# Sheet.net
KiCad netlist of a schematic drawn in Altium Designer
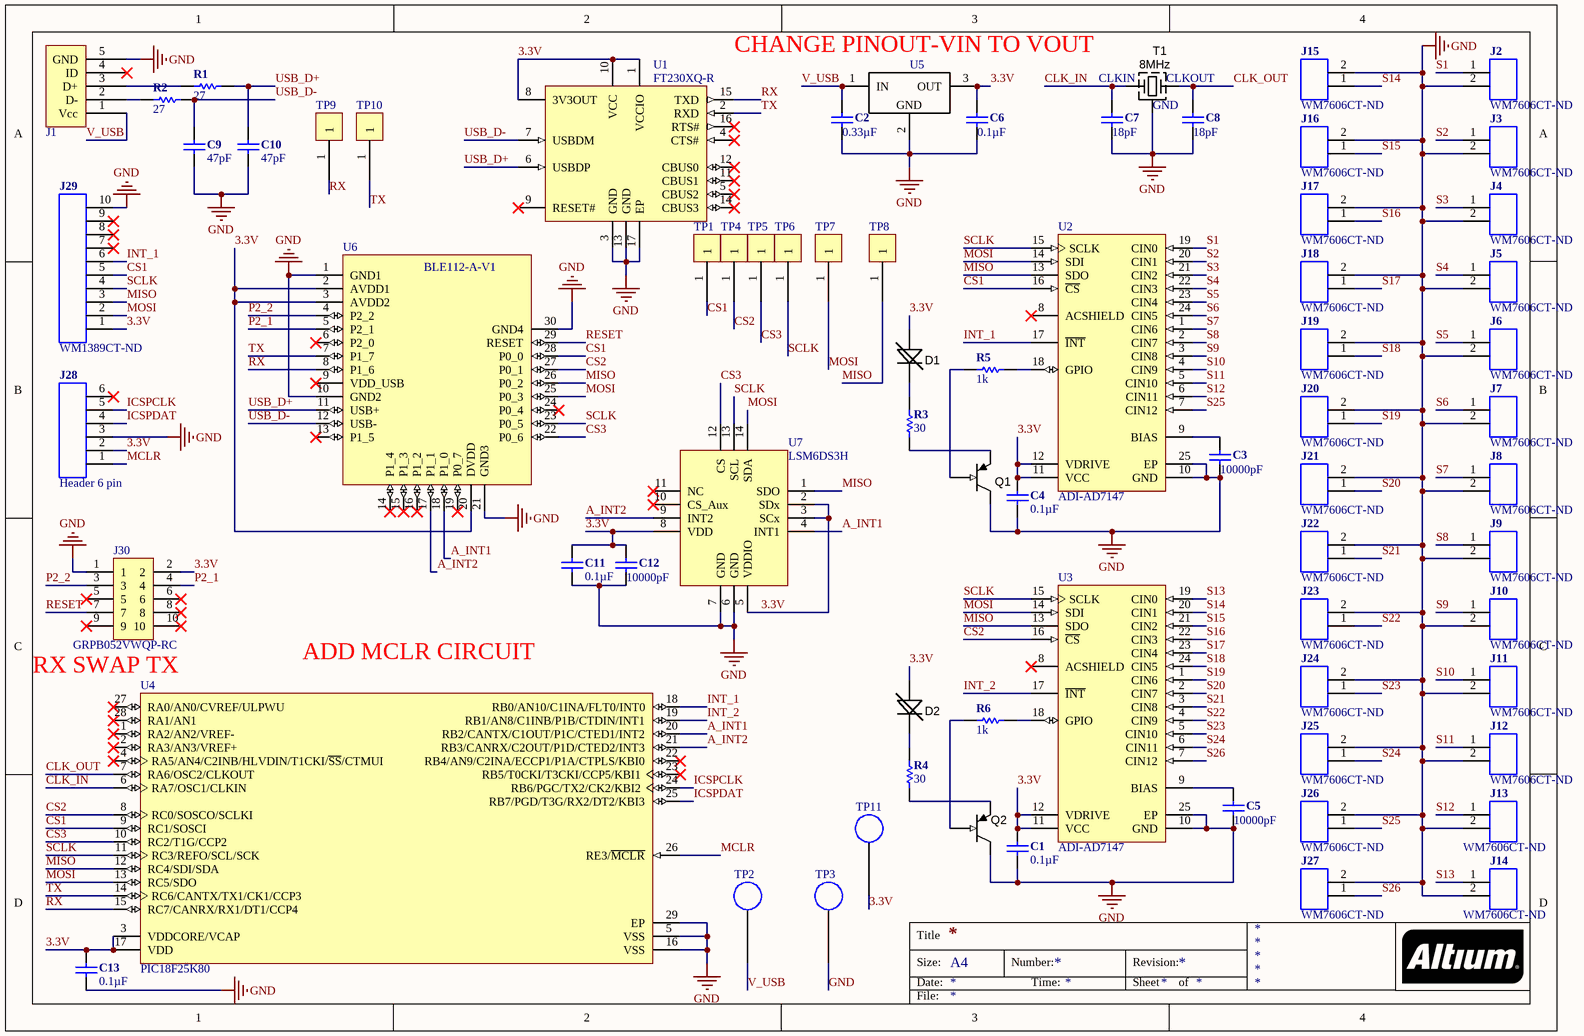
[diagram p0: Sheet.SchDoc]

(export (version "E")
  (design (tool "Eeschema 10.0.6"))
  (components
    (comp (ref "C1")
      (value "0.1µF")
      (footprint "CAP-0805(2012)-R")
      (description "___ OHM ___ mW 0805(2012) SMD")
      (fields
        (field (name "MANUFACTURER") "Yageo")
        (field (name "MANUFACTURER PART NUMBER") "CC0805KRX7R9BB104")
      )
      (libsource (lib "Glove") (part "C-0805(2012)"))
    )
    (comp (ref "C2")
      (value "0.33µF")
      (footprint "CAP-0805(2012)-R")
      (description "___ OHM ___ mW 0805(2012) SMD")
      (fields
        (field (name "MANUFACTURER") "Yageo")
        (field (name "MANUFACTURER PART NUMBER") "CC0805KKX7R7BB334")
      )
      (libsource (lib "Glove") (part "C-0805(2012)"))
    )
    (comp (ref "C3")
      (value "10000pF")
      (footprint "CAP-0805(2012)-R")
      (description "___ OHM ___ mW 0805(2012) SMD")
      (fields
        (field (name "MANUFACTURER") "Yageo")
        (field (name "MANUFACTURER PART NUMBER") "CC0805KRX7R9BB103")
      )
      (libsource (lib "Glove") (part "C-0805(2012)"))
    )
    (comp (ref "C4")
      (value "0.1µF")
      (footprint "CAP-0805(2012)-R")
      (description "___ OHM ___ mW 0805(2012) SMD")
      (fields
        (field (name "MANUFACTURER") "Yageo")
        (field (name "MANUFACTURER PART NUMBER") "CC0805KRX7R9BB104")
      )
      (libsource (lib "Glove") (part "C-0805(2012)"))
    )
    (comp (ref "C5")
      (value "10000pF")
      (footprint "CAP-0805(2012)-R")
      (description "___ OHM ___ mW 0805(2012) SMD")
      (fields
        (field (name "MANUFACTURER") "Yageo")
        (field (name "MANUFACTURER PART NUMBER") "CC0805KRX7R9BB103")
      )
      (libsource (lib "Glove") (part "C-0805(2012)"))
    )
    (comp (ref "C6")
      (value "0.1µF")
      (footprint "CAP-0805(2012)-R")
      (description "___ OHM ___ mW 0805(2012) SMD")
      (fields
        (field (name "MANUFACTURER") "Yageo")
        (field (name "MANUFACTURER PART NUMBER") "CC0805KRX7R9BB104")
      )
      (libsource (lib "Glove") (part "C-0805(2012)"))
    )
    (comp (ref "C7")
      (value "18pF")
      (footprint "CAP-0805(2012)-R")
      (description "___ OHM ___ mW 0805(2012) SMD")
      (fields
        (field (name "MANUFACTURER") "Yageo")
        (field (name "MANUFACTURER PART NUMBER") "CC0805JRNPO9BN180")
      )
      (libsource (lib "Glove") (part "C-0805(2012)"))
    )
    (comp (ref "C8")
      (value "18pF")
      (footprint "CAP-0805(2012)-R")
      (description "___ OHM ___ mW 0805(2012) SMD")
      (fields
        (field (name "MANUFACTURER") "Yageo")
        (field (name "MANUFACTURER PART NUMBER") "CC0805JRNPO9BN180")
      )
      (libsource (lib "Glove") (part "C-0805(2012)"))
    )
    (comp (ref "C9")
      (value "47pF")
      (footprint "CAP-0805(2012)-R")
      (description "___ OHM ___ mW 0805(2012) SMD")
      (fields
        (field (name "MANUFACTURER") "Yageo")
        (field (name "MANUFACTURER PART NUMBER") "CC0805JRNPO9BN470")
      )
      (libsource (lib "Glove") (part "C-0805(2012)"))
    )
    (comp (ref "C10")
      (value "47pF")
      (footprint "CAP-0805(2012)-R")
      (description "___ OHM ___ mW 0805(2012) SMD")
      (fields
        (field (name "MANUFACTURER") "Yageo")
        (field (name "MANUFACTURER PART NUMBER") "CC0805JRNPO9BN470")
      )
      (libsource (lib "Glove") (part "C-0805(2012)"))
    )
    (comp (ref "C11")
      (value "0.1µF")
      (footprint "CAP-0805(2012)-R")
      (description "___ OHM ___ mW 0805(2012) SMD")
      (fields
        (field (name "MANUFACTURER") "Yageo")
        (field (name "MANUFACTURER PART NUMBER") "CC0805KRX7R9BB104")
      )
      (libsource (lib "Glove") (part "C-0805(2012)"))
    )
    (comp (ref "C12")
      (value "10000pF")
      (footprint "CAP-0805(2012)-R")
      (description "___ OHM ___ mW 0805(2012) SMD")
      (fields
        (field (name "MANUFACTURER") "Yageo")
        (field (name "MANUFACTURER PART NUMBER") "CC0805KRX7R9BB103")
      )
      (libsource (lib "Glove") (part "C-0805(2012)"))
    )
    (comp (ref "C13")
      (value "0.1µF")
      (footprint "CAP-0805(2012)-R")
      (description "___ OHM ___ mW 0805(2012) SMD")
      (fields
        (field (name "MANUFACTURER") "Yageo")
        (field (name "MANUFACTURER PART NUMBER") "CC0805KRX7R9BB104")
      )
      (libsource (lib "Glove") (part "C-0805(2012)"))
    )
    (comp (ref "D1")
      (value "YELLOW")
      (footprint "LED-0805-A")
      (description "LED, 0805 SMD, YELLOW")
      (fields
        (field (name "MANUFACTURER") "OSRAM Opto Semiconductors Inc.")
        (field (name "MANUFACTURER PART NUMBER") "LY R976-PS-36")
      )
      (libsource (lib "Glove") (part "LED_0805_YELLOW"))
    )
    (comp (ref "D2")
      (value "YELLOW")
      (footprint "LED-0805-A")
      (description "LED, 0805 SMD, YELLOW")
      (fields
        (field (name "MANUFACTURER") "OSRAM Opto Semiconductors Inc.")
        (field (name "MANUFACTURER PART NUMBER") "LY R976-PS-36")
      )
      (libsource (lib "Glove") (part "LED_0805_YELLOW"))
    )
    (comp (ref "J1")
      (value "USB")
      (footprint "USB_Connector_5P_MICRO_USB_FCI")
      (description "USB_Connector_5P_MICRO_USB_FCI")
      (fields
        (field (name "MANUFACTURER") "Amphenol FCI")
        (field (name "MANUFACTURER PART NUMBER") "10118194-0001LF")
      )
      (libsource (lib "Glove") (part "USB"))
    )
    (comp (ref "J2")
      (value "Header 2 pin")
      (footprint "WM7606CT-ND")
      (description "Header, 2 pin, .1 pitch")
      (fields
        (field (name "MANUFACTURER") "Molex, LLC")
        (field (name "MANUFACTURER PART NUMBER") "0533980271")
        (field (name "SUPPLIER PART NUMBER 1") "WM7606CT-ND")
      )
      (libsource (lib "") (part "CON-2Pin_1"))
    )
    (comp (ref "J3")
      (value "Header 2 pin")
      (footprint "WM7606CT-ND")
      (description "Header, 2 pin, .1 pitch")
      (fields
        (field (name "MANUFACTURER") "Molex, LLC")
        (field (name "MANUFACTURER PART NUMBER") "0533980271")
        (field (name "SUPPLIER PART NUMBER 1") "WM7606CT-ND")
      )
      (libsource (lib "") (part "CON-2Pin_1"))
    )
    (comp (ref "J4")
      (value "Header 2 pin")
      (footprint "WM7606CT-ND")
      (description "Header, 2 pin, .1 pitch")
      (fields
        (field (name "MANUFACTURER") "Molex, LLC")
        (field (name "MANUFACTURER PART NUMBER") "0533980271")
        (field (name "SUPPLIER PART NUMBER 1") "WM7606CT-ND")
      )
      (libsource (lib "") (part "CON-2Pin_1"))
    )
    (comp (ref "J5")
      (value "Header 2 pin")
      (footprint "WM7606CT-ND")
      (description "Header, 2 pin, .1 pitch")
      (fields
        (field (name "MANUFACTURER") "Molex, LLC")
        (field (name "MANUFACTURER PART NUMBER") "0533980271")
        (field (name "SUPPLIER PART NUMBER 1") "WM7606CT-ND")
      )
      (libsource (lib "") (part "CON-2Pin_1"))
    )
    (comp (ref "J6")
      (value "Header 2 pin")
      (footprint "WM7606CT-ND")
      (description "Header, 2 pin, .1 pitch")
      (fields
        (field (name "MANUFACTURER") "Molex, LLC")
        (field (name "MANUFACTURER PART NUMBER") "0533980271")
        (field (name "SUPPLIER PART NUMBER 1") "WM7606CT-ND")
      )
      (libsource (lib "") (part "CON-2Pin_1"))
    )
    (comp (ref "J7")
      (value "Header 2 pin")
      (footprint "WM7606CT-ND")
      (description "Header, 2 pin, .1 pitch")
      (fields
        (field (name "MANUFACTURER") "Molex, LLC")
        (field (name "MANUFACTURER PART NUMBER") "0533980271")
        (field (name "SUPPLIER PART NUMBER 1") "WM7606CT-ND")
      )
      (libsource (lib "") (part "CON-2Pin_1"))
    )
    (comp (ref "J8")
      (value "Header 2 pin")
      (footprint "WM7606CT-ND")
      (description "Header, 2 pin, .1 pitch")
      (fields
        (field (name "MANUFACTURER") "Molex, LLC")
        (field (name "MANUFACTURER PART NUMBER") "0533980271")
        (field (name "SUPPLIER PART NUMBER 1") "WM7606CT-ND")
      )
      (libsource (lib "") (part "CON-2Pin_1"))
    )
    (comp (ref "J9")
      (value "Header 2 pin")
      (footprint "WM7606CT-ND")
      (description "Header, 2 pin, .1 pitch")
      (fields
        (field (name "MANUFACTURER") "Molex, LLC")
        (field (name "MANUFACTURER PART NUMBER") "0533980271")
        (field (name "SUPPLIER PART NUMBER 1") "WM7606CT-ND")
      )
      (libsource (lib "") (part "CON-2Pin_1"))
    )
    (comp (ref "J10")
      (value "Header 2 pin")
      (footprint "WM7606CT-ND")
      (description "Header, 2 pin, .1 pitch")
      (fields
        (field (name "MANUFACTURER") "Molex, LLC")
        (field (name "MANUFACTURER PART NUMBER") "0533980271")
        (field (name "SUPPLIER PART NUMBER 1") "WM7606CT-ND")
      )
      (libsource (lib "") (part "CON-2Pin_1"))
    )
    (comp (ref "J11")
      (value "Header 2 pin")
      (footprint "WM7606CT-ND")
      (description "Header, 2 pin, .1 pitch")
      (fields
        (field (name "MANUFACTURER") "Molex, LLC")
        (field (name "MANUFACTURER PART NUMBER") "0533980271")
        (field (name "SUPPLIER PART NUMBER 1") "WM7606CT-ND")
      )
      (libsource (lib "") (part "CON-2Pin_1"))
    )
    (comp (ref "J12")
      (value "Header 2 pin")
      (footprint "WM7606CT-ND")
      (description "Header, 2 pin, .1 pitch")
      (fields
        (field (name "MANUFACTURER") "Molex, LLC")
        (field (name "MANUFACTURER PART NUMBER") "0533980271")
        (field (name "SUPPLIER PART NUMBER 1") "WM7606CT-ND")
      )
      (libsource (lib "") (part "CON-2Pin_1"))
    )
    (comp (ref "J13")
      (value "Header 2 pin")
      (footprint "WM7606CT-ND")
      (description "Header, 2 pin, .1 pitch")
      (fields
        (field (name "MANUFACTURER") "Molex, LLC")
        (field (name "MANUFACTURER PART NUMBER") "0533980271")
        (field (name "SUPPLIER PART NUMBER 1") "WM7606CT-ND")
      )
      (libsource (lib "") (part "CON-2Pin_1"))
    )
    (comp (ref "J14")
      (value "Header 2 pin")
      (footprint "WM7606CT-ND")
      (description "Header, 2 pin, .1 pitch")
      (fields
        (field (name "MANUFACTURER") "Molex, LLC")
        (field (name "MANUFACTURER PART NUMBER") "0533980271")
        (field (name "SUPPLIER PART NUMBER 1") "WM7606CT-ND")
      )
      (libsource (lib "") (part "CON-2Pin_1"))
    )
    (comp (ref "J15")
      (value "Header 2 pin")
      (footprint "WM7606CT-ND")
      (description "Header, 2 pin, .1 pitch")
      (fields
        (field (name "MANUFACTURER") "Molex, LLC")
        (field (name "MANUFACTURER PART NUMBER") "0533980271")
        (field (name "SUPPLIER PART NUMBER 1") "WM7606CT-ND")
      )
      (libsource (lib "Glove") (part "CON-2Pin"))
    )
    (comp (ref "J16")
      (value "Header 2 pin")
      (footprint "WM7606CT-ND")
      (description "Header, 2 pin, .1 pitch")
      (fields
        (field (name "MANUFACTURER") "Molex, LLC")
        (field (name "MANUFACTURER PART NUMBER") "0533980271")
        (field (name "SUPPLIER PART NUMBER 1") "WM7606CT-ND")
      )
      (libsource (lib "Glove") (part "CON-2Pin"))
    )
    (comp (ref "J17")
      (value "Header 2 pin")
      (footprint "WM7606CT-ND")
      (description "Header, 2 pin, .1 pitch")
      (fields
        (field (name "MANUFACTURER") "Molex, LLC")
        (field (name "MANUFACTURER PART NUMBER") "0533980271")
        (field (name "SUPPLIER PART NUMBER 1") "WM7606CT-ND")
      )
      (libsource (lib "Glove") (part "CON-2Pin"))
    )
    (comp (ref "J18")
      (value "Header 2 pin")
      (footprint "WM7606CT-ND")
      (description "Header, 2 pin, .1 pitch")
      (fields
        (field (name "MANUFACTURER") "Molex, LLC")
        (field (name "MANUFACTURER PART NUMBER") "0533980271")
        (field (name "SUPPLIER PART NUMBER 1") "WM7606CT-ND")
      )
      (libsource (lib "Glove") (part "CON-2Pin"))
    )
    (comp (ref "J19")
      (value "Header 2 pin")
      (footprint "WM7606CT-ND")
      (description "Header, 2 pin, .1 pitch")
      (fields
        (field (name "MANUFACTURER") "Molex, LLC")
        (field (name "MANUFACTURER PART NUMBER") "0533980271")
        (field (name "SUPPLIER PART NUMBER 1") "WM7606CT-ND")
      )
      (libsource (lib "Glove") (part "CON-2Pin"))
    )
    (comp (ref "J20")
      (value "Header 2 pin")
      (footprint "WM7606CT-ND")
      (description "Header, 2 pin, .1 pitch")
      (fields
        (field (name "MANUFACTURER") "Molex, LLC")
        (field (name "MANUFACTURER PART NUMBER") "0533980271")
        (field (name "SUPPLIER PART NUMBER 1") "WM7606CT-ND")
      )
      (libsource (lib "Glove") (part "CON-2Pin"))
    )
    (comp (ref "J21")
      (value "Header 2 pin")
      (footprint "WM7606CT-ND")
      (description "Header, 2 pin, .1 pitch")
      (fields
        (field (name "MANUFACTURER") "Molex, LLC")
        (field (name "MANUFACTURER PART NUMBER") "0533980271")
        (field (name "SUPPLIER PART NUMBER 1") "WM7606CT-ND")
      )
      (libsource (lib "Glove") (part "CON-2Pin"))
    )
    (comp (ref "J22")
      (value "Header 2 pin")
      (footprint "WM7606CT-ND")
      (description "Header, 2 pin, .1 pitch")
      (fields
        (field (name "MANUFACTURER") "Molex, LLC")
        (field (name "MANUFACTURER PART NUMBER") "0533980271")
        (field (name "SUPPLIER PART NUMBER 1") "WM7606CT-ND")
      )
      (libsource (lib "Glove") (part "CON-2Pin"))
    )
    (comp (ref "J23")
      (value "Header 2 pin")
      (footprint "WM7606CT-ND")
      (description "Header, 2 pin, .1 pitch")
      (fields
        (field (name "MANUFACTURER") "Molex, LLC")
        (field (name "MANUFACTURER PART NUMBER") "0533980271")
        (field (name "SUPPLIER PART NUMBER 1") "WM7606CT-ND")
      )
      (libsource (lib "Glove") (part "CON-2Pin"))
    )
    (comp (ref "J24")
      (value "Header 2 pin")
      (footprint "WM7606CT-ND")
      (description "Header, 2 pin, .1 pitch")
      (fields
        (field (name "MANUFACTURER") "Molex, LLC")
        (field (name "MANUFACTURER PART NUMBER") "0533980271")
        (field (name "SUPPLIER PART NUMBER 1") "WM7606CT-ND")
      )
      (libsource (lib "Glove") (part "CON-2Pin"))
    )
    (comp (ref "J25")
      (value "Header 2 pin")
      (footprint "WM7606CT-ND")
      (description "Header, 2 pin, .1 pitch")
      (fields
        (field (name "MANUFACTURER") "Molex, LLC")
        (field (name "MANUFACTURER PART NUMBER") "0533980271")
        (field (name "SUPPLIER PART NUMBER 1") "WM7606CT-ND")
      )
      (libsource (lib "Glove") (part "CON-2Pin"))
    )
    (comp (ref "J26")
      (value "Header 2 pin")
      (footprint "WM7606CT-ND")
      (description "Header, 2 pin, .1 pitch")
      (fields
        (field (name "MANUFACTURER") "Molex, LLC")
        (field (name "MANUFACTURER PART NUMBER") "0533980271")
        (field (name "SUPPLIER PART NUMBER 1") "WM7606CT-ND")
      )
      (libsource (lib "Glove") (part "CON-2Pin"))
    )
    (comp (ref "J27")
      (value "Header 2 pin")
      (footprint "WM7606CT-ND")
      (description "Header, 2 pin, .1 pitch")
      (fields
        (field (name "MANUFACTURER") "Molex, LLC")
        (field (name "MANUFACTURER PART NUMBER") "0533980271")
        (field (name "SUPPLIER PART NUMBER 1") "WM7606CT-ND")
      )
      (libsource (lib "Glove") (part "CON-2Pin"))
    )
    (comp (ref "J28")
      (value "Header 6 pin")
      (footprint "HEADER-6-100mil")
      (description "Header, 6 pin, .1 pitch")
      (fields
        (field (name "MANUFACTURER") "Amphenol FCI")
        (field (name "MANUFACTURER PART NUMBER") "68000-406HLF")
      )
      (libsource (lib "Glove") (part "CON-6Pin-100Mil"))
    )
    (comp (ref "J29")
      (value "Header 10 pin")
      (footprint "MOLEX-503480-1000")
      (description "Header, 10 pin, .50mm pitch")
      (fields
        (field (name "MANUFACTURER") "Molex, LLC")
        (field (name "MANUFACTURER PART NUMBER") "5034801000")
        (field (name "SUPPLIER PART NUMBER 1") "WM1389CT-ND")
      )
      (libsource (lib "Glove") (part "WM1389CT-ND"))
    )
    (comp (ref "J30")
      (value "GRPB052VWQP-RC")
      (footprint "GRPB052VWQP-RC")
      (description "CONN HEADER .050\" 10PS DL SMD AU")
      (fields (field (name "MANUFACTURER") "Sullins Connector Solutions"))
      (libsource (lib "UCSD Protolab") (part "GRPB052VWQP-RC"))
    )
    (comp (ref "Q1")
      (value "~")
      (footprint "SOT23-3")
      (description "Transistor PNP")
      (fields
        (field (name "MANUFACTURER") "Diodes Incorporated")
        (field (name "MANUFACTURER PART NUMBER") "FMMT591TA")
      )
      (libsource (lib "Glove") (part "FMMT591CT-ND"))
    )
    (comp (ref "Q2")
      (value "~")
      (footprint "SOT23-3")
      (description "Transistor PNP")
      (fields
        (field (name "MANUFACTURER") "Diodes Incorporated")
        (field (name "MANUFACTURER PART NUMBER") "FMMT591TA")
      )
      (libsource (lib "Glove") (part "FMMT591CT-ND"))
    )
    (comp (ref "R1")
      (value "27")
      (footprint "R-0805(2012)-R")
      (description "___ OHM ___ mW 0805(2012) SMD")
      (fields
        (field (name "MANUFACTURER") "Yageo")
        (field (name "MANUFACTURER PART NUMBER") "RC0805JR-0727RL")
      )
      (libsource (lib "Glove") (part "R-0805(2012)"))
    )
    (comp (ref "R2")
      (value "27")
      (footprint "R-0805(2012)-R")
      (description "___ OHM ___ mW 0805(2012) SMD")
      (fields
        (field (name "MANUFACTURER") "Yageo")
        (field (name "MANUFACTURER PART NUMBER") "RC0805JR-0727RL")
      )
      (libsource (lib "Glove") (part "R-0805(2012)"))
    )
    (comp (ref "R3")
      (value "30")
      (footprint "R-0805(2012)-R")
      (description "___ OHM ___ mW 0805(2012) SMD")
      (fields
        (field (name "MANUFACTURER") "Yageo")
        (field (name "MANUFACTURER PART NUMBER") "RC0805JR-0730RL")
      )
      (libsource (lib "Glove") (part "R-0805(2012)"))
    )
    (comp (ref "R4")
      (value "30")
      (footprint "R-0805(2012)-R")
      (description "___ OHM ___ mW 0805(2012) SMD")
      (fields
        (field (name "MANUFACTURER") "Yageo")
        (field (name "MANUFACTURER PART NUMBER") "RC0805JR-0730RL")
      )
      (libsource (lib "Glove") (part "R-0805(2012)"))
    )
    (comp (ref "R5")
      (value "1k")
      (footprint "R-0805(2012)-R")
      (description "___ OHM ___ mW 0805(2012) SMD")
      (fields
        (field (name "MANUFACTURER") "Yageo")
        (field (name "MANUFACTURER PART NUMBER") "RC0805JR-071KL")
      )
      (libsource (lib "Glove") (part "R-0805(2012)"))
    )
    (comp (ref "R6")
      (value "1k")
      (footprint "R-0805(2012)-R")
      (description "___ OHM ___ mW 0805(2012) SMD")
      (fields
        (field (name "MANUFACTURER") "Yageo")
        (field (name "MANUFACTURER PART NUMBER") "RC0805JR-071KL")
      )
      (libsource (lib "Glove") (part "R-0805(2012)"))
    )
    (comp (ref "T1")
      (value "8MHz")
      (footprint "CRYSTAL-8MHZ")
      (description "Oscillator Crystal 8MHz 10ppm")
      (fields
        (field (name "MANUFACTURER") "Abracon LLC")
        (field (name "MANUFACTURER PART NUMBER") "ABMM2-8.000MHZ-E2-T")
      )
      (libsource (lib "Glove") (part "CRYSTAL_8MHz"))
    )
    (comp (ref "TP1")
      (value "Test Point")
      (footprint "Test Point")
      (description "Test Point Hole")
      (fields
        (field (name "MANUFACTURER") "Keystone Electronics")
        (field (name "MANUFACTURER PART NUMBER") "5000")
      )
      (libsource (lib "Glove") (part "Test Point"))
    )
    (comp (ref "TP2")
      (value "S1751-46R")
      (footprint "S1751-46R")
      (description "PC TEST POINT TIN SMD")
      (fields (field (name "MANUFACTURER") "Harwin Inc."))
      (libsource (lib "Glove") (part "S1751-46R"))
    )
    (comp (ref "TP3")
      (value "S1751-46R")
      (footprint "S1751-46R")
      (description "PC TEST POINT TIN SMD")
      (fields (field (name "MANUFACTURER") "Harwin Inc."))
      (libsource (lib "Glove") (part "S1751-46R"))
    )
    (comp (ref "TP4")
      (value "Test Point")
      (footprint "Test Point")
      (description "Test Point Hole")
      (fields
        (field (name "MANUFACTURER") "Keystone Electronics")
        (field (name "MANUFACTURER PART NUMBER") "5000")
      )
      (libsource (lib "Glove") (part "Test Point"))
    )
    (comp (ref "TP5")
      (value "Test Point")
      (footprint "Test Point")
      (description "Test Point Hole")
      (fields
        (field (name "MANUFACTURER") "Keystone Electronics")
        (field (name "MANUFACTURER PART NUMBER") "5000")
      )
      (libsource (lib "Glove") (part "Test Point"))
    )
    (comp (ref "TP6")
      (value "Test Point")
      (footprint "Test Point")
      (description "Test Point Hole")
      (fields
        (field (name "MANUFACTURER") "Keystone Electronics")
        (field (name "MANUFACTURER PART NUMBER") "5000")
      )
      (libsource (lib "Glove") (part "Test Point"))
    )
    (comp (ref "TP7")
      (value "Test Point")
      (footprint "Test Point")
      (description "Test Point Hole")
      (fields
        (field (name "MANUFACTURER") "Keystone Electronics")
        (field (name "MANUFACTURER PART NUMBER") "5000")
      )
      (libsource (lib "Glove") (part "Test Point"))
    )
    (comp (ref "TP8")
      (value "Test Point")
      (footprint "Test Point")
      (description "Test Point Hole")
      (fields
        (field (name "MANUFACTURER") "Keystone Electronics")
        (field (name "MANUFACTURER PART NUMBER") "5000")
      )
      (libsource (lib "Glove") (part "Test Point"))
    )
    (comp (ref "TP9")
      (value "Test Point")
      (footprint "Test Point")
      (description "Test Point Hole")
      (fields
        (field (name "MANUFACTURER") "Keystone Electronics")
        (field (name "MANUFACTURER PART NUMBER") "5000")
      )
      (libsource (lib "Glove") (part "Test Point"))
    )
    (comp (ref "TP10")
      (value "Test Point")
      (footprint "Test Point")
      (description "Test Point Hole")
      (fields
        (field (name "MANUFACTURER") "Keystone Electronics")
        (field (name "MANUFACTURER PART NUMBER") "5000")
      )
      (libsource (lib "Glove") (part "Test Point"))
    )
    (comp (ref "TP11")
      (value "S1751-46R")
      (footprint "S1751-46R")
      (description "PC TEST POINT TIN SMD")
      (fields (field (name "MANUFACTURER") "Harwin Inc."))
      (libsource (lib "Glove") (part "S1751-46R"))
    )
    (comp (ref "U1")
      (value "FT230XQ-R")
      (footprint "QFN-16")
      (fields (field (name "MANUFACTURER") "FTDI, Future Technology Devices International Ltd"))
      (libsource (lib "Glove") (part "FT230XQ-R"))
    )
    (comp (ref "U2")
      (value "ADI-AD7147")
      (footprint "LFCSP_WQ")
      (fields
        (field (name "MANUFACTURER") "Analog Devices Inc.")
        (field (name "MANUFACTURER PART NUMBER") "AD7147PACPZ-500R7")
      )
      (libsource (lib "Glove") (part "ADI-AD7147"))
    )
    (comp (ref "U3")
      (value "ADI-AD7147")
      (footprint "LFCSP_WQ")
      (fields
        (field (name "MANUFACTURER") "Analog Devices Inc.")
        (field (name "MANUFACTURER PART NUMBER") "AD7147PACPZ-500R7")
      )
      (libsource (lib "Glove") (part "ADI-AD7147"))
    )
    (comp (ref "U4")
      (value "PIC18F25K80")
      (footprint "MCHP-QFN-S-MM28_N")
      (fields
        (field (name "MANUFACTURER") "Microchip Technology")
        (field (name "MANUFACTURER PART NUMBER") "PIC18F25K80T-I/MM")
      )
      (libsource (lib "Glove") (part "PIC18F25K80"))
    )
    (comp (ref "U5")
      (value "L78L33ACUTR")
      (footprint "SOT89-3")
      (fields (field (name "MANUFACTURER") "STMicroelectronics"))
      (libsource (lib "Glove") (part "L78L33ACUTR"))
    )
    (comp (ref "U6")
      (value "BLE112-A-V1")
      (footprint "BLE112-A-V1")
      (description "CLASS 2 BLTOOTH 4.0 MODULE")
      (fields (field (name "MANUFACTURER") "Silicon Labs"))
      (libsource (lib "UCSD Protolab") (part "BLE112-A-V1"))
    )
    (comp (ref "U7")
      (value "LSM6DS3H")
      (footprint "LGA-14")
      (description "3D accelerometer and 3D gyroscope")
      (fields
        (field (name "MANUFACTURER") "STMicroelectronics")
        (field (name "MANUFACTURER PART NUMBER") "LSM6DS3HTR")
      )
      (libsource (lib "Glove") (part "LSM6DS3H"))
    )
  )
  (nets
    (net (code "1") (name "/3.3V") (class "Default")
      (node (ref "C1") (pin "1") (pinfunction "1_1") (pintype "passive"))
      (node (ref "C11") (pin "2") (pinfunction "2_2") (pintype "passive"))
      (node (ref "C12") (pin "2") (pinfunction "2_2") (pintype "passive"))
      (node (ref "C13") (pin "1") (pinfunction "1_1") (pintype "passive"))
      (node (ref "C4") (pin "1") (pinfunction "1_1") (pintype "passive"))
      (node (ref "C6") (pin "1") (pinfunction "1_1") (pintype "passive"))
      (node (ref "D1") (pin "A") (pinfunction "A_A") (pintype "passive"))
      (node (ref "D2") (pin "A") (pinfunction "A_A") (pintype "passive"))
      (node (ref "J28") (pin "2") (pinfunction "2_2") (pintype "passive"))
      (node (ref "J29") (pin "1") (pinfunction "1_1") (pintype "passive"))
      (node (ref "J30") (pin "2") (pinfunction "2_2") (pintype "passive"))
      (node (ref "TP11") (pin "1") (pinfunction "1_1") (pintype "passive"))
      (node (ref "U1") (pin "1") (pinfunction "VCCIO_1") (pintype "power_in"))
      (node (ref "U1") (pin "10") (pinfunction "VCC_10") (pintype "power_in"))
      (node (ref "U1") (pin "8") (pinfunction "3V3OUT_8") (pintype "power_in"))
      (node (ref "U2") (pin "11") (pinfunction "VCC_11") (pintype "power_in"))
      (node (ref "U2") (pin "12") (pinfunction "VDRIVE_12") (pintype "power_in"))
      (node (ref "U3") (pin "11") (pinfunction "VCC_11") (pintype "power_in"))
      (node (ref "U3") (pin "12") (pinfunction "VDRIVE_12") (pintype "power_in"))
      (node (ref "U4") (pin "17") (pinfunction "VDD_17") (pintype "power_in"))
      (node (ref "U4") (pin "3") (pinfunction "VDDCORE/VCAP_3") (pintype "power_in"))
      (node (ref "U5") (pin "3") (pinfunction "OUT_3") (pintype "power_in"))
      (node (ref "U6") (pin "2") (pinfunction "AVDD1_2") (pintype "power_in"))
      (node (ref "U6") (pin "20") (pinfunction "DVDD_20") (pintype "power_in"))
      (node (ref "U6") (pin "3") (pinfunction "AVDD2_3") (pintype "power_in"))
      (node (ref "U7") (pin "2") (pinfunction "SDx_2") (pintype "passive"))
      (node (ref "U7") (pin "3") (pinfunction "SCx_3") (pintype "passive"))
      (node (ref "U7") (pin "5") (pinfunction "VDDIO_5") (pintype "passive"))
      (node (ref "U7") (pin "8") (pinfunction "VDD_8") (pintype "passive"))
    )
    (net (code "2") (name "/A_INT1") (class "Default")
      (node (ref "U4") (pin "20") (pinfunction "RB2/CANTX/C1OUT/P1C/CTED1/INT2_20") (pintype "bidirectional"))
      (node (ref "U6") (pin "18") (pinfunction "P1_0_18") (pintype "bidirectional"))
      (node (ref "U7") (pin "4") (pinfunction "INT1_4") (pintype "passive"))
    )
    (net (code "3") (name "/A_INT2") (class "Default")
      (node (ref "U4") (pin "21") (pinfunction "RB3/CANRX/C2OUT/P1D/CTED2/INT3_21") (pintype "bidirectional"))
      (node (ref "U6") (pin "17") (pinfunction "P1_1_17") (pintype "bidirectional"))
      (node (ref "U7") (pin "9") (pinfunction "INT2_9") (pintype "passive"))
    )
    (net (code "4") (name "/CLK_IN") (class "Default")
      (node (ref "C7") (pin "1") (pinfunction "1_1") (pintype "passive"))
      (node (ref "T1") (pin "1") (pinfunction "CLKIN_1") (pintype "passive"))
      (node (ref "U4") (pin "6") (pinfunction "RA7/OSC1/CLKIN_6") (pintype "bidirectional"))
    )
    (net (code "5") (name "/CLK_OUT") (class "Default")
      (node (ref "C8") (pin "1") (pinfunction "1_1") (pintype "passive"))
      (node (ref "T1") (pin "3") (pinfunction "X_3") (pintype "passive"))
      (node (ref "U4") (pin "7") (pinfunction "RA6/OSC2/CLKOUT_7") (pintype "bidirectional"))
    )
    (net (code "6") (name "/CS1") (class "Default")
      (node (ref "J29") (pin "5") (pinfunction "5_5") (pintype "passive"))
      (node (ref "TP1") (pin "1") (pinfunction "1_1") (pintype "passive"))
      (node (ref "U2") (pin "16") (pinfunction "~{CS}_16") (pintype "input"))
      (node (ref "U4") (pin "9") (pinfunction "RC1/SOSCI_9") (pintype "bidirectional"))
      (node (ref "U6") (pin "28") (pinfunction "P0_0_28") (pintype "bidirectional"))
    )
    (net (code "7") (name "/CS2") (class "Default")
      (node (ref "TP4") (pin "1") (pinfunction "1_1") (pintype "passive"))
      (node (ref "U3") (pin "16") (pinfunction "~{CS}_16") (pintype "input"))
      (node (ref "U4") (pin "8") (pinfunction "RC0/SOSCO/SCLKI_8") (pintype "bidirectional"))
      (node (ref "U6") (pin "27") (pinfunction "P0_1_27") (pintype "bidirectional"))
    )
    (net (code "8") (name "/CS3") (class "Default")
      (node (ref "TP5") (pin "1") (pinfunction "1_1") (pintype "passive"))
      (node (ref "U4") (pin "10") (pinfunction "RC2/T1G/CCP2_10") (pintype "bidirectional"))
      (node (ref "U6") (pin "22") (pinfunction "P0_6_22") (pintype "bidirectional"))
      (node (ref "U7") (pin "12") (pinfunction "CS_12") (pintype "passive"))
    )
    (net (code "9") (name "/ICSPCLK") (class "Default")
      (node (ref "J28") (pin "5") (pinfunction "5_5") (pintype "passive"))
      (node (ref "U4") (pin "24") (pinfunction "RB6/PGC/TX2/CK2/KBI2_24") (pintype "bidirectional"))
    )
    (net (code "10") (name "/ICSPDAT") (class "Default")
      (node (ref "J28") (pin "4") (pinfunction "4_4") (pintype "passive"))
      (node (ref "U4") (pin "25") (pinfunction "RB7/PGD/T3G/RX2/DT2/KBI3_25") (pintype "bidirectional"))
    )
    (net (code "11") (name "/INT_1") (class "Default")
      (node (ref "J29") (pin "6") (pinfunction "6_6") (pintype "passive"))
      (node (ref "U2") (pin "17") (pinfunction "~{INT}_17") (pintype "open_collector"))
      (node (ref "U4") (pin "18") (pinfunction "RB0/AN10/C1INA/FLT0/INT0_18") (pintype "bidirectional"))
    )
    (net (code "12") (name "/INT_2") (class "Default")
      (node (ref "U3") (pin "17") (pinfunction "~{INT}_17") (pintype "open_collector"))
      (node (ref "U4") (pin "19") (pinfunction "RB1/AN8/C1INB/P1B/CTDIN/INT1_19") (pintype "bidirectional"))
    )
    (net (code "13") (name "/MCLR") (class "Default")
      (node (ref "J28") (pin "1") (pinfunction "1_1") (pintype "passive"))
      (node (ref "U4") (pin "26") (pinfunction "RE3/~{MCLR}_26") (pintype "input"))
    )
    (net (code "14") (name "/MISO") (class "Default")
      (node (ref "J29") (pin "3") (pinfunction "3_3") (pintype "passive"))
      (node (ref "TP8") (pin "1") (pinfunction "1_1") (pintype "passive"))
      (node (ref "U2") (pin "13") (pinfunction "SDO_13") (pintype "tri_state"))
      (node (ref "U3") (pin "13") (pinfunction "SDO_13") (pintype "tri_state"))
      (node (ref "U4") (pin "12") (pinfunction "RC4/SDI/SDA_12") (pintype "bidirectional"))
      (node (ref "U6") (pin "26") (pinfunction "P0_2_26") (pintype "bidirectional"))
      (node (ref "U7") (pin "1") (pinfunction "SDO_1") (pintype "passive"))
    )
    (net (code "15") (name "/MOSI") (class "Default")
      (node (ref "J29") (pin "2") (pinfunction "2_2") (pintype "passive"))
      (node (ref "TP7") (pin "1") (pinfunction "1_1") (pintype "passive"))
      (node (ref "U2") (pin "14") (pinfunction "SDI_14") (pintype "input"))
      (node (ref "U3") (pin "14") (pinfunction "SDI_14") (pintype "input"))
      (node (ref "U4") (pin "13") (pinfunction "RC5/SDO_13") (pintype "bidirectional"))
      (node (ref "U6") (pin "25") (pinfunction "P0_3_25") (pintype "bidirectional"))
      (node (ref "U7") (pin "14") (pinfunction "SDA_14") (pintype "passive"))
    )
    (net (code "16") (name "/P2_1") (class "Default")
      (node (ref "J30") (pin "4") (pinfunction "4_4") (pintype "passive"))
      (node (ref "U6") (pin "5") (pinfunction "P2_1_5") (pintype "bidirectional"))
    )
    (net (code "17") (name "/P2_2") (class "Default")
      (node (ref "J30") (pin "3") (pinfunction "3_3") (pintype "passive"))
      (node (ref "U6") (pin "4") (pinfunction "P2_2_4") (pintype "bidirectional"))
    )
    (net (code "18") (name "/RESET") (class "Default")
      (node (ref "J30") (pin "7") (pinfunction "7_7") (pintype "passive"))
      (node (ref "U6") (pin "29") (pinfunction "RESET_29") (pintype "bidirectional"))
    )
    (net (code "19") (name "/RX") (class "Default")
      (node (ref "TP9") (pin "1") (pinfunction "1_1") (pintype "passive"))
      (node (ref "U1") (pin "15") (pinfunction "TXD_15") (pintype "output"))
      (node (ref "U4") (pin "15") (pinfunction "RC7/CANRX/RX1/DT1/CCP4_15") (pintype "bidirectional"))
      (node (ref "U6") (pin "8") (pinfunction "P1_6_8") (pintype "bidirectional"))
    )
    (net (code "20") (name "/S1") (class "Default")
      (node (ref "J2") (pin "1") (pinfunction "1_1") (pintype "passive"))
      (node (ref "U2") (pin "19") (pinfunction "CIN0_19") (pintype "input"))
    )
    (net (code "21") (name "/S2") (class "Default")
      (node (ref "J3") (pin "1") (pinfunction "1_1") (pintype "passive"))
      (node (ref "U2") (pin "20") (pinfunction "CIN1_20") (pintype "input"))
    )
    (net (code "22") (name "/S3") (class "Default")
      (node (ref "J4") (pin "1") (pinfunction "1_1") (pintype "passive"))
      (node (ref "U2") (pin "21") (pinfunction "CIN2_21") (pintype "input"))
    )
    (net (code "23") (name "/S4") (class "Default")
      (node (ref "J5") (pin "1") (pinfunction "1_1") (pintype "passive"))
      (node (ref "U2") (pin "22") (pinfunction "CIN3_22") (pintype "input"))
    )
    (net (code "24") (name "/S5") (class "Default")
      (node (ref "J6") (pin "1") (pinfunction "1_1") (pintype "passive"))
      (node (ref "U2") (pin "23") (pinfunction "CIN4_23") (pintype "input"))
    )
    (net (code "25") (name "/S6") (class "Default")
      (node (ref "J7") (pin "1") (pinfunction "1_1") (pintype "passive"))
      (node (ref "U2") (pin "24") (pinfunction "CIN5_24") (pintype "input"))
    )
    (net (code "26") (name "/S7") (class "Default")
      (node (ref "J8") (pin "1") (pinfunction "1_1") (pintype "passive"))
      (node (ref "U2") (pin "1") (pinfunction "CIN6_1") (pintype "input"))
    )
    (net (code "27") (name "/S8") (class "Default")
      (node (ref "J9") (pin "1") (pinfunction "1_1") (pintype "passive"))
      (node (ref "U2") (pin "2") (pinfunction "CIN7_2") (pintype "input"))
    )
    (net (code "28") (name "/S9") (class "Default")
      (node (ref "J10") (pin "1") (pinfunction "1_1") (pintype "passive"))
      (node (ref "U2") (pin "3") (pinfunction "CIN8_3") (pintype "input"))
    )
    (net (code "29") (name "/S10") (class "Default")
      (node (ref "J11") (pin "1") (pinfunction "1_1") (pintype "passive"))
      (node (ref "U2") (pin "4") (pinfunction "CIN9_4") (pintype "input"))
    )
    (net (code "30") (name "/S11") (class "Default")
      (node (ref "J12") (pin "1") (pinfunction "1_1") (pintype "passive"))
      (node (ref "U2") (pin "5") (pinfunction "CIN10_5") (pintype "input"))
    )
    (net (code "31") (name "/S12") (class "Default")
      (node (ref "J13") (pin "1") (pinfunction "1_1") (pintype "passive"))
      (node (ref "U2") (pin "6") (pinfunction "CIN11_6") (pintype "input"))
    )
    (net (code "32") (name "/S13") (class "Default")
      (node (ref "J14") (pin "1") (pinfunction "1_1") (pintype "passive"))
      (node (ref "U3") (pin "19") (pinfunction "CIN0_19") (pintype "input"))
    )
    (net (code "33") (name "/S14") (class "Default")
      (node (ref "J15") (pin "1") (pinfunction "1_1") (pintype "passive"))
      (node (ref "U3") (pin "20") (pinfunction "CIN1_20") (pintype "input"))
    )
    (net (code "34") (name "/S15") (class "Default")
      (node (ref "J16") (pin "1") (pinfunction "1_1") (pintype "passive"))
      (node (ref "U3") (pin "21") (pinfunction "CIN2_21") (pintype "input"))
    )
    (net (code "35") (name "/S16") (class "Default")
      (node (ref "J17") (pin "1") (pinfunction "1_1") (pintype "passive"))
      (node (ref "U3") (pin "22") (pinfunction "CIN3_22") (pintype "input"))
    )
    (net (code "36") (name "/S17") (class "Default")
      (node (ref "J18") (pin "1") (pinfunction "1_1") (pintype "passive"))
      (node (ref "U3") (pin "23") (pinfunction "CIN4_23") (pintype "input"))
    )
    (net (code "37") (name "/S18") (class "Default")
      (node (ref "J19") (pin "1") (pinfunction "1_1") (pintype "passive"))
      (node (ref "U3") (pin "24") (pinfunction "CIN5_24") (pintype "input"))
    )
    (net (code "38") (name "/S19") (class "Default")
      (node (ref "J20") (pin "1") (pinfunction "1_1") (pintype "passive"))
      (node (ref "U3") (pin "1") (pinfunction "CIN6_1") (pintype "input"))
    )
    (net (code "39") (name "/S20") (class "Default")
      (node (ref "J21") (pin "1") (pinfunction "1_1") (pintype "passive"))
      (node (ref "U3") (pin "2") (pinfunction "CIN7_2") (pintype "input"))
    )
    (net (code "40") (name "/S21") (class "Default")
      (node (ref "J22") (pin "1") (pinfunction "1_1") (pintype "passive"))
      (node (ref "U3") (pin "3") (pinfunction "CIN8_3") (pintype "input"))
    )
    (net (code "41") (name "/S22") (class "Default")
      (node (ref "J23") (pin "1") (pinfunction "1_1") (pintype "passive"))
      (node (ref "U3") (pin "4") (pinfunction "CIN9_4") (pintype "input"))
    )
    (net (code "42") (name "/S23") (class "Default")
      (node (ref "J24") (pin "1") (pinfunction "1_1") (pintype "passive"))
      (node (ref "U3") (pin "5") (pinfunction "CIN10_5") (pintype "input"))
    )
    (net (code "43") (name "/S24") (class "Default")
      (node (ref "J25") (pin "1") (pinfunction "1_1") (pintype "passive"))
      (node (ref "U3") (pin "6") (pinfunction "CIN11_6") (pintype "input"))
    )
    (net (code "44") (name "/S25") (class "Default")
      (node (ref "J26") (pin "1") (pinfunction "1_1") (pintype "passive"))
      (node (ref "U2") (pin "7") (pinfunction "CIN12_7") (pintype "input"))
    )
    (net (code "45") (name "/S26") (class "Default")
      (node (ref "J27") (pin "1") (pinfunction "1_1") (pintype "passive"))
      (node (ref "U3") (pin "7") (pinfunction "CIN12_7") (pintype "input"))
    )
    (net (code "46") (name "/SCLK") (class "Default")
      (node (ref "J29") (pin "4") (pinfunction "4_4") (pintype "passive"))
      (node (ref "TP6") (pin "1") (pinfunction "1_1") (pintype "passive"))
      (node (ref "U2") (pin "15") (pinfunction "SCLK_15") (pintype "input"))
      (node (ref "U3") (pin "15") (pinfunction "SCLK_15") (pintype "input"))
      (node (ref "U4") (pin "11") (pinfunction "RC3/REFO/SCL/SCK_11") (pintype "bidirectional"))
      (node (ref "U6") (pin "23") (pinfunction "P0_5_23") (pintype "bidirectional"))
      (node (ref "U7") (pin "13") (pinfunction "SCL_13") (pintype "passive"))
    )
    (net (code "47") (name "/TX") (class "Default")
      (node (ref "TP10") (pin "1") (pinfunction "1_1") (pintype "passive"))
      (node (ref "U1") (pin "2") (pinfunction "RXD_2") (pintype "input"))
      (node (ref "U4") (pin "14") (pinfunction "RC6/CANTX/TX1/CK1/CCP3_14") (pintype "bidirectional"))
      (node (ref "U6") (pin "7") (pinfunction "P1_7_7") (pintype "bidirectional"))
    )
    (net (code "48") (name "/USB_D+") (class "Default")
      (node (ref "C10") (pin "2") (pinfunction "2_2") (pintype "passive"))
      (node (ref "R1") (pin "2") (pinfunction "2_2") (pintype "passive"))
      (node (ref "U1") (pin "6") (pinfunction "USBDP_6") (pintype "input"))
      (node (ref "U6") (pin "11") (pinfunction "USB+_11") (pintype "bidirectional"))
    )
    (net (code "49") (name "/USB_D-") (class "Default")
      (node (ref "C9") (pin "2") (pinfunction "2_2") (pintype "passive"))
      (node (ref "R2") (pin "2") (pinfunction "2_2") (pintype "passive"))
      (node (ref "U1") (pin "7") (pinfunction "USBDM_7") (pintype "input"))
      (node (ref "U6") (pin "12") (pinfunction "USB-_12") (pintype "bidirectional"))
    )
    (net (code "50") (name "/V_USB") (class "Default")
      (node (ref "C2") (pin "1") (pinfunction "1_1") (pintype "passive"))
      (node (ref "J1") (pin "1") (pinfunction "Vcc_1") (pintype "passive"))
      (node (ref "TP2") (pin "1") (pinfunction "1_1") (pintype "passive"))
      (node (ref "U5") (pin "1") (pinfunction "IN_1") (pintype "passive"))
    )
    (net (code "51") (name "GND") (class "Default")
      (node (ref "C1") (pin "2") (pinfunction "2_2") (pintype "passive"))
      (node (ref "C10") (pin "1") (pinfunction "1_1") (pintype "passive"))
      (node (ref "C11") (pin "1") (pinfunction "1_1") (pintype "passive"))
      (node (ref "C12") (pin "1") (pinfunction "1_1") (pintype "passive"))
      (node (ref "C13") (pin "2") (pinfunction "2_2") (pintype "passive"))
      (node (ref "C2") (pin "2") (pinfunction "2_2") (pintype "passive"))
      (node (ref "C3") (pin "2") (pinfunction "2_2") (pintype "passive"))
      (node (ref "C4") (pin "2") (pinfunction "2_2") (pintype "passive"))
      (node (ref "C5") (pin "2") (pinfunction "2_2") (pintype "passive"))
      (node (ref "C6") (pin "2") (pinfunction "2_2") (pintype "passive"))
      (node (ref "C7") (pin "2") (pinfunction "2_2") (pintype "passive"))
      (node (ref "C8") (pin "2") (pinfunction "2_2") (pintype "passive"))
      (node (ref "C9") (pin "1") (pinfunction "1_1") (pintype "passive"))
      (node (ref "J1") (pin "5") (pinfunction "GND_5") (pintype "passive"))
      (node (ref "J10") (pin "2") (pinfunction "2_2") (pintype "passive"))
      (node (ref "J11") (pin "2") (pinfunction "2_2") (pintype "passive"))
      (node (ref "J12") (pin "2") (pinfunction "2_2") (pintype "passive"))
      (node (ref "J13") (pin "2") (pinfunction "2_2") (pintype "passive"))
      (node (ref "J14") (pin "2") (pinfunction "2_2") (pintype "passive"))
      (node (ref "J15") (pin "2") (pinfunction "2_2") (pintype "passive"))
      (node (ref "J16") (pin "2") (pinfunction "2_2") (pintype "passive"))
      (node (ref "J17") (pin "2") (pinfunction "2_2") (pintype "passive"))
      (node (ref "J18") (pin "2") (pinfunction "2_2") (pintype "passive"))
      (node (ref "J19") (pin "2") (pinfunction "2_2") (pintype "passive"))
      (node (ref "J2") (pin "2") (pinfunction "2_2") (pintype "passive"))
      (node (ref "J20") (pin "2") (pinfunction "2_2") (pintype "passive"))
      (node (ref "J21") (pin "2") (pinfunction "2_2") (pintype "passive"))
      (node (ref "J22") (pin "2") (pinfunction "2_2") (pintype "passive"))
      (node (ref "J23") (pin "2") (pinfunction "2_2") (pintype "passive"))
      (node (ref "J24") (pin "2") (pinfunction "2_2") (pintype "passive"))
      (node (ref "J25") (pin "2") (pinfunction "2_2") (pintype "passive"))
      (node (ref "J26") (pin "2") (pinfunction "2_2") (pintype "passive"))
      (node (ref "J27") (pin "2") (pinfunction "2_2") (pintype "passive"))
      (node (ref "J28") (pin "3") (pinfunction "3_3") (pintype "passive"))
      (node (ref "J29") (pin "10") (pinfunction "10_10") (pintype "passive"))
      (node (ref "J3") (pin "2") (pinfunction "2_2") (pintype "passive"))
      (node (ref "J30") (pin "1") (pinfunction "1_1") (pintype "passive"))
      (node (ref "J4") (pin "2") (pinfunction "2_2") (pintype "passive"))
      (node (ref "J5") (pin "2") (pinfunction "2_2") (pintype "passive"))
      (node (ref "J6") (pin "2") (pinfunction "2_2") (pintype "passive"))
      (node (ref "J7") (pin "2") (pinfunction "2_2") (pintype "passive"))
      (node (ref "J8") (pin "2") (pinfunction "2_2") (pintype "passive"))
      (node (ref "J9") (pin "2") (pinfunction "2_2") (pintype "passive"))
      (node (ref "Q1") (pin "2") (pinfunction "C_2") (pintype "passive"))
      (node (ref "Q2") (pin "2") (pinfunction "C_2") (pintype "passive"))
      (node (ref "T1") (pin "2") (pinfunction "GND_2") (pintype "passive"))
      (node (ref "TP3") (pin "1") (pinfunction "1_1") (pintype "passive"))
      (node (ref "U1") (pin "13") (pinfunction "GND_13") (pintype "power_in"))
      (node (ref "U1") (pin "17") (pinfunction "EP_17") (pintype "power_in"))
      (node (ref "U1") (pin "3") (pinfunction "GND_3") (pintype "power_in"))
      (node (ref "U2") (pin "10") (pinfunction "GND_10") (pintype "power_in"))
      (node (ref "U2") (pin "25") (pinfunction "EP_25") (pintype "power_in"))
      (node (ref "U3") (pin "10") (pinfunction "GND_10") (pintype "power_in"))
      (node (ref "U3") (pin "25") (pinfunction "EP_25") (pintype "power_in"))
      (node (ref "U4") (pin "16") (pinfunction "VSS_16") (pintype "power_in"))
      (node (ref "U4") (pin "29") (pinfunction "EP_29") (pintype "power_in"))
      (node (ref "U4") (pin "5") (pinfunction "VSS_5") (pintype "power_in"))
      (node (ref "U5") (pin "2") (pinfunction "GND_2") (pintype "power_in"))
      (node (ref "U6") (pin "1") (pinfunction "GND1_1") (pintype "power_in"))
      (node (ref "U6") (pin "10") (pinfunction "GND2_10") (pintype "power_in"))
      (node (ref "U6") (pin "21") (pinfunction "GND3_21") (pintype "power_in"))
      (node (ref "U6") (pin "30") (pinfunction "GND4_30") (pintype "power_in"))
      (node (ref "U7") (pin "6") (pinfunction "GND_6") (pintype "passive"))
      (node (ref "U7") (pin "7") (pinfunction "GND_7") (pintype "passive"))
    )
    (net (code "52") (name "Net-(D1-PadK)") (class "Default")
      (node (ref "D1") (pin "K") (pinfunction "K_K") (pintype "passive"))
      (node (ref "R3") (pin "2") (pinfunction "2_2") (pintype "passive"))
    )
    (net (code "53") (name "Net-(D2-PadK)") (class "Default")
      (node (ref "D2") (pin "K") (pinfunction "K_K") (pintype "passive"))
      (node (ref "R4") (pin "2") (pinfunction "2_2") (pintype "passive"))
    )
    (net (code "54") (name "Net-(J1-D+)") (class "Default")
      (node (ref "J1") (pin "3") (pinfunction "D+_3") (pintype "passive"))
      (node (ref "R1") (pin "1") (pinfunction "1_1") (pintype "passive"))
    )
    (net (code "55") (name "Net-(J1-D-)") (class "Default")
      (node (ref "J1") (pin "2") (pinfunction "D-_2") (pintype "passive"))
      (node (ref "R2") (pin "1") (pinfunction "1_1") (pintype "passive"))
    )
    (net (code "56") (name "Net-(Q1-B)") (class "Default")
      (node (ref "Q1") (pin "1") (pinfunction "B_1") (pintype "input"))
      (node (ref "R5") (pin "1") (pinfunction "1_1") (pintype "passive"))
    )
    (net (code "57") (name "Net-(Q1-E)") (class "Default")
      (node (ref "Q1") (pin "3") (pinfunction "E_3") (pintype "passive"))
      (node (ref "R3") (pin "1") (pinfunction "1_1") (pintype "passive"))
    )
    (net (code "58") (name "Net-(Q2-B)") (class "Default")
      (node (ref "Q2") (pin "1") (pinfunction "B_1") (pintype "input"))
      (node (ref "R6") (pin "2") (pinfunction "2_2") (pintype "passive"))
    )
    (net (code "59") (name "Net-(Q2-E)") (class "Default")
      (node (ref "Q2") (pin "3") (pinfunction "E_3") (pintype "passive"))
      (node (ref "R4") (pin "1") (pinfunction "1_1") (pintype "passive"))
    )
    (net (code "60") (name "Net-(U2-BIAS)") (class "Default")
      (node (ref "C3") (pin "1") (pinfunction "1_1") (pintype "passive"))
      (node (ref "U2") (pin "9") (pinfunction "BIAS_9") (pintype "passive"))
    )
    (net (code "61") (name "Net-(U2-GPIO)") (class "Default")
      (node (ref "R5") (pin "2") (pinfunction "2_2") (pintype "passive"))
      (node (ref "U2") (pin "18") (pinfunction "GPIO_18") (pintype "bidirectional"))
    )
    (net (code "62") (name "Net-(U3-BIAS)") (class "Default")
      (node (ref "C5") (pin "1") (pinfunction "1_1") (pintype "passive"))
      (node (ref "U3") (pin "9") (pinfunction "BIAS_9") (pintype "passive"))
    )
    (net (code "63") (name "Net-(U3-GPIO)") (class "Default")
      (node (ref "R6") (pin "1") (pinfunction "1_1") (pintype "passive"))
      (node (ref "U3") (pin "18") (pinfunction "GPIO_18") (pintype "bidirectional"))
    )
    (net (code "64") (name "unconnected-(J1-ID-Pad4)") (class "Default")
      (node (ref "J1") (pin "4") (pinfunction "ID_4") (pintype "passive+no_connect"))
    )
    (net (code "65") (name "unconnected-(J28-Pad6)") (class "Default")
      (node (ref "J28") (pin "6") (pinfunction "6_6") (pintype "passive+no_connect"))
    )
    (net (code "66") (name "unconnected-(J29-Pad7)") (class "Default")
      (node (ref "J29") (pin "7") (pinfunction "7_7") (pintype "passive+no_connect"))
    )
    (net (code "67") (name "unconnected-(J29-Pad8)") (class "Default")
      (node (ref "J29") (pin "8") (pinfunction "8_8") (pintype "passive+no_connect"))
    )
    (net (code "68") (name "unconnected-(J29-Pad9)") (class "Default")
      (node (ref "J29") (pin "9") (pinfunction "9_9") (pintype "passive+no_connect"))
    )
    (net (code "69") (name "unconnected-(J30-Pad5)") (class "Default")
      (node (ref "J30") (pin "5") (pinfunction "5_5") (pintype "passive+no_connect"))
    )
    (net (code "70") (name "unconnected-(J30-Pad6)") (class "Default")
      (node (ref "J30") (pin "6") (pinfunction "6_6") (pintype "passive+no_connect"))
    )
    (net (code "71") (name "unconnected-(J30-Pad8)") (class "Default")
      (node (ref "J30") (pin "8") (pinfunction "8_8") (pintype "passive+no_connect"))
    )
    (net (code "72") (name "unconnected-(J30-Pad9)") (class "Default")
      (node (ref "J30") (pin "9") (pinfunction "9_9") (pintype "passive+no_connect"))
    )
    (net (code "73") (name "unconnected-(J30-Pad10)") (class "Default")
      (node (ref "J30") (pin "10") (pinfunction "10_10") (pintype "passive+no_connect"))
    )
    (net (code "74") (name "unconnected-(U1-CBUS0-Pad12)") (class "Default")
      (node (ref "U1") (pin "12") (pinfunction "CBUS0_12") (pintype "bidirectional+no_connect"))
    )
    (net (code "75") (name "unconnected-(U1-CBUS1-Pad11)") (class "Default")
      (node (ref "U1") (pin "11") (pinfunction "CBUS1_11") (pintype "bidirectional+no_connect"))
    )
    (net (code "76") (name "unconnected-(U1-CBUS2-Pad5)") (class "Default")
      (node (ref "U1") (pin "5") (pinfunction "CBUS2_5") (pintype "bidirectional+no_connect"))
    )
    (net (code "77") (name "unconnected-(U1-CBUS3-Pad14)") (class "Default")
      (node (ref "U1") (pin "14") (pinfunction "CBUS3_14") (pintype "bidirectional+no_connect"))
    )
    (net (code "78") (name "unconnected-(U1-CTS#-Pad4)") (class "Default")
      (node (ref "U1") (pin "4") (pinfunction "CTS#_4") (pintype "input+no_connect"))
    )
    (net (code "79") (name "unconnected-(U1-RESET#-Pad9)") (class "Default")
      (node (ref "U1") (pin "9") (pinfunction "RESET#_9") (pintype "passive+no_connect"))
    )
    (net (code "80") (name "unconnected-(U1-RTS#-Pad16)") (class "Default")
      (node (ref "U1") (pin "16") (pinfunction "RTS#_16") (pintype "output+no_connect"))
    )
    (net (code "81") (name "unconnected-(U2-ACSHIELD-Pad8)") (class "Default")
      (node (ref "U2") (pin "8") (pinfunction "ACSHIELD_8") (pintype "passive+no_connect"))
    )
    (net (code "82") (name "unconnected-(U3-ACSHIELD-Pad8)") (class "Default")
      (node (ref "U3") (pin "8") (pinfunction "ACSHIELD_8") (pintype "passive+no_connect"))
    )
    (net (code "83") (name "unconnected-(U4-RA0{slash}AN0{slash}CVREF{slash}ULPWU-Pad27)") (class "Default")
      (node (ref "U4") (pin "27") (pinfunction "RA0/AN0/CVREF/ULPWU_27") (pintype "bidirectional+no_connect"))
    )
    (net (code "84") (name "unconnected-(U4-RA1{slash}AN1-Pad28)") (class "Default")
      (node (ref "U4") (pin "28") (pinfunction "RA1/AN1_28") (pintype "bidirectional+no_connect"))
    )
    (net (code "85") (name "unconnected-(U4-RA2{slash}AN2{slash}VREF--Pad1)") (class "Default")
      (node (ref "U4") (pin "1") (pinfunction "RA2/AN2/VREF-_1") (pintype "bidirectional+no_connect"))
    )
    (net (code "86") (name "unconnected-(U4-RA3{slash}AN3{slash}VREF+-Pad2)") (class "Default")
      (node (ref "U4") (pin "2") (pinfunction "RA3/AN3/VREF+_2") (pintype "bidirectional+no_connect"))
    )
    (net (code "87") (name "unconnected-(U4-RA5{slash}AN4{slash}C2INB{slash}HLVDIN{slash}T1CKI{slash}~{SS}{slash}CTMUI-Pad4)") (class "Default")
      (node (ref "U4") (pin "4") (pinfunction "RA5/AN4/C2INB/HLVDIN/T1CKI/~{SS}/CTMUI_4") (pintype "bidirectional+no_connect"))
    )
    (net (code "88") (name "unconnected-(U4-RB4{slash}AN9{slash}C2INA{slash}ECCP1{slash}P1A{slash}CTPLS{slash}KBI0-Pad22)") (class "Default")
      (node (ref "U4") (pin "22") (pinfunction "RB4/AN9/C2INA/ECCP1/P1A/CTPLS/KBI0_22") (pintype "bidirectional+no_connect"))
    )
    (net (code "89") (name "unconnected-(U4-RB5{slash}T0CKI{slash}T3CKI{slash}CCP5{slash}KBI1-Pad23)") (class "Default")
      (node (ref "U4") (pin "23") (pinfunction "RB5/T0CKI/T3CKI/CCP5/KBI1_23") (pintype "bidirectional+no_connect"))
    )
    (net (code "90") (name "unconnected-(U6-P0_4-Pad24)") (class "Default")
      (node (ref "U6") (pin "24") (pinfunction "P0_4_24") (pintype "bidirectional+no_connect"))
    )
    (net (code "91") (name "unconnected-(U6-P0_7-Pad19)") (class "Default")
      (node (ref "U6") (pin "19") (pinfunction "P0_7_19") (pintype "bidirectional+no_connect"))
    )
    (net (code "92") (name "unconnected-(U6-P1_2-Pad16)") (class "Default")
      (node (ref "U6") (pin "16") (pinfunction "P1_2_16") (pintype "bidirectional+no_connect"))
    )
    (net (code "93") (name "unconnected-(U6-P1_3-Pad15)") (class "Default")
      (node (ref "U6") (pin "15") (pinfunction "P1_3_15") (pintype "bidirectional+no_connect"))
    )
    (net (code "94") (name "unconnected-(U6-P1_4-Pad14)") (class "Default")
      (node (ref "U6") (pin "14") (pinfunction "P1_4_14") (pintype "bidirectional+no_connect"))
    )
    (net (code "95") (name "unconnected-(U6-P1_5-Pad13)") (class "Default")
      (node (ref "U6") (pin "13") (pinfunction "P1_5_13") (pintype "bidirectional+no_connect"))
    )
    (net (code "96") (name "unconnected-(U6-P2_0-Pad6)") (class "Default")
      (node (ref "U6") (pin "6") (pinfunction "P2_0_6") (pintype "bidirectional+no_connect"))
    )
    (net (code "97") (name "unconnected-(U6-VDD_USB-Pad9)") (class "Default")
      (node (ref "U6") (pin "9") (pinfunction "VDD_USB_9") (pintype "power_in+no_connect"))
    )
    (net (code "98") (name "unconnected-(U7-CS_Aux-Pad10)") (class "Default")
      (node (ref "U7") (pin "10") (pinfunction "CS_Aux_10") (pintype "passive+no_connect"))
    )
    (net (code "99") (name "unconnected-(U7-NC-Pad11)") (class "Default")
      (node (ref "U7") (pin "11") (pinfunction "NC_11") (pintype "passive+no_connect"))
    )
  )
)
